# Power_Supply.net
KiCad netlist of a schematic drawn in Altium Designer
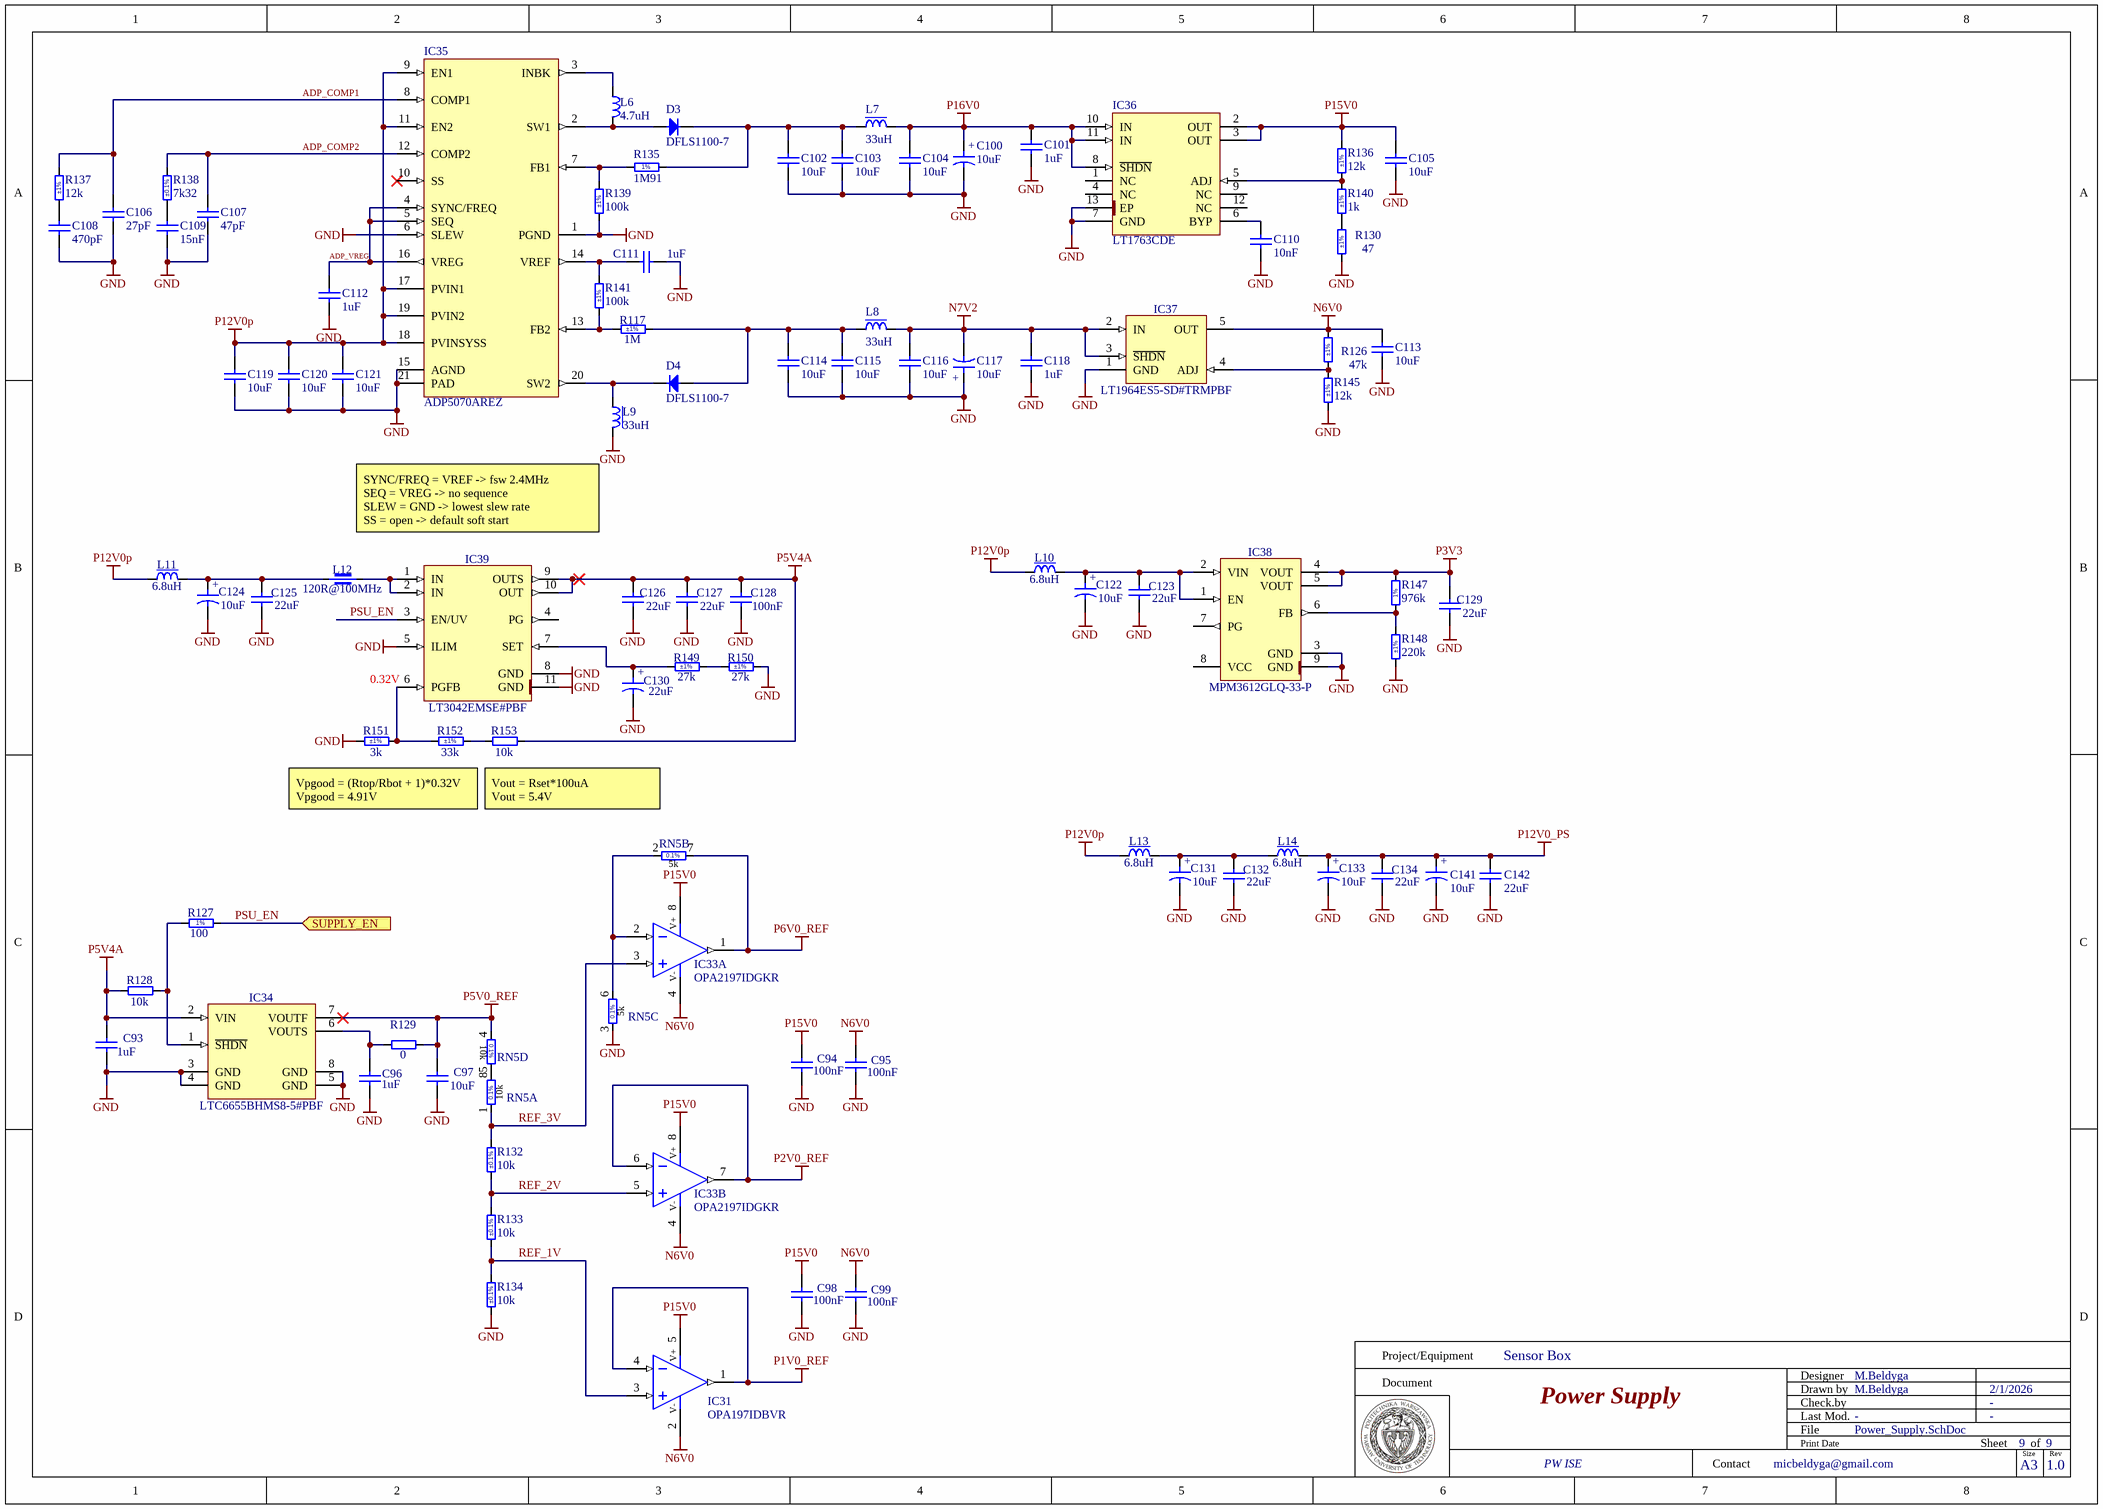
[diagram p0: Power_Supply.SchDoc]

(export (version "E")
  (design (tool "Eeschema 10.0.6"))
  (components
    (comp (ref "C93")
      (value "1uF")
      (footprint "CAPC1608X87N")
      (description "Non-polarised capacitor")
      (fields
        (field (name "PART NUMBER") "CC0603_1UF_25V_10%_X7R")
        (field (name "VOLTAGE") "25V")
        (field (name "AUTHOR") "CERN DEM JLC")
      )
      (libsource (lib "Capacitors") (part "Capacitor - non polarized"))
    )
    (comp (ref "C94")
      (value "100nF")
      (footprint "CAPC1005X55N")
      (description "Non-polarised capacitor")
      (fields
        (field (name "PART NUMBER") "CC0402_100NF_16V_10%_X5R")
        (field (name "VOLTAGE") "16V")
        (field (name "AUTHOR") "CERN DEM JLC")
      )
      (libsource (lib "Capacitors") (part "Capacitor - non polarized"))
    )
    (comp (ref "C95")
      (value "100nF")
      (footprint "CAPC1005X55N")
      (description "Non-polarised capacitor")
      (fields
        (field (name "PART NUMBER") "CC0402_100NF_16V_10%_X5R")
        (field (name "VOLTAGE") "16V")
        (field (name "AUTHOR") "CERN DEM JLC")
      )
      (libsource (lib "Capacitors") (part "Capacitor - non polarized"))
    )
    (comp (ref "C96")
      (value "1uF")
      (footprint "CAPC1608X87N")
      (description "Non-polarised capacitor")
      (fields
        (field (name "PART NUMBER") "CC0603_1UF_25V_10%_X7R")
        (field (name "VOLTAGE") "25V")
        (field (name "AUTHOR") "CERN DEM JLC")
      )
      (libsource (lib "Capacitors") (part "Capacitor - non polarized"))
    )
    (comp (ref "C97")
      (value "10uF")
      (footprint "CAPC1608X80N")
      (description "Non-polarised capacitor")
      (fields
        (field (name "PART NUMBER") "CC0603_10UF_16V_20%_X5R")
        (field (name "VOLTAGE") "16V")
        (field (name "AUTHOR") "CERN DEM MR")
      )
      (libsource (lib "Capacitors") (part "Capacitor - non polarized"))
    )
    (comp (ref "C98")
      (value "100nF")
      (footprint "CAPC1005X55N")
      (description "Non-polarised capacitor")
      (fields
        (field (name "PART NUMBER") "CC0402_100NF_16V_10%_X5R")
        (field (name "VOLTAGE") "16V")
        (field (name "AUTHOR") "CERN DEM JLC")
      )
      (libsource (lib "Capacitors") (part "Capacitor - non polarized"))
    )
    (comp (ref "C99")
      (value "100nF")
      (footprint "CAPC1005X55N")
      (description "Non-polarised capacitor")
      (fields
        (field (name "PART NUMBER") "CC0402_100NF_16V_10%_X5R")
        (field (name "VOLTAGE") "16V")
        (field (name "AUTHOR") "CERN DEM JLC")
      )
      (libsource (lib "Capacitors") (part "Capacitor - non polarized"))
    )
    (comp (ref "C100")
      (value "10uF")
      (footprint "CAPMP3216X180N")
      (description "Polarised capacitor")
      (fields
        (field (name "PART NUMBER") "CTE3216-18_10UF_16V_20%_AVX_TCJ")
        (field (name "VOLTAGE") "16V")
        (field (name "AUTHOR") "CERN DEM JLC")
      )
      (libsource (lib "Capacitors") (part "Capacitor - polarized"))
    )
    (comp (ref "C101")
      (value "1uF")
      (footprint "CAPC1608X87N")
      (description "Non-polarised capacitor")
      (fields
        (field (name "PART NUMBER") "CC0603_1UF_25V_10%_X7R")
        (field (name "VOLTAGE") "25V")
        (field (name "AUTHOR") "CERN DEM JLC")
      )
      (libsource (lib "Capacitors") (part "Capacitor - non polarized"))
    )
    (comp (ref "C102")
      (value "10uF")
      (footprint "CAPC1709X100N")
      (description "Non-polarised capacitor")
      (fields
        (field (name "PART NUMBER") "CC0603_10UF_25V_20%_X5R")
        (field (name "VOLTAGE") "25V")
        (field (name "AUTHOR") "CERN DEM BC")
      )
      (libsource (lib "Capacitors") (part "Capacitor - non polarized"))
    )
    (comp (ref "C103")
      (value "10uF")
      (footprint "CAPC1709X100N")
      (description "Non-polarised capacitor")
      (fields
        (field (name "PART NUMBER") "CC0603_10UF_25V_20%_X5R")
        (field (name "VOLTAGE") "25V")
        (field (name "AUTHOR") "CERN DEM BC")
      )
      (libsource (lib "Capacitors") (part "Capacitor - non polarized"))
    )
    (comp (ref "C104")
      (value "10uF")
      (footprint "CAPC1709X100N")
      (description "Non-polarised capacitor")
      (fields
        (field (name "PART NUMBER") "CC0603_10UF_25V_20%_X5R")
        (field (name "VOLTAGE") "25V")
        (field (name "AUTHOR") "CERN DEM BC")
      )
      (libsource (lib "Capacitors") (part "Capacitor - non polarized"))
    )
    (comp (ref "C105")
      (value "10uF")
      (footprint "CAPC1709X100N")
      (description "Non-polarised capacitor")
      (fields
        (field (name "PART NUMBER") "CC0603_10UF_25V_20%_X5R")
        (field (name "VOLTAGE") "25V")
        (field (name "AUTHOR") "CERN DEM BC")
      )
      (libsource (lib "Capacitors") (part "Capacitor - non polarized"))
    )
    (comp (ref "C106")
      (value "27pF")
      (footprint "CAPC1005X55N")
      (description "Non-polarised capacitor")
      (fields
        (field (name "PART NUMBER") "CC0402_27PF_50V_5%_C0G")
        (field (name "VOLTAGE") "50V")
        (field (name "AUTHOR") "CERN DEM JLC")
      )
      (libsource (lib "Capacitors") (part "Capacitor - non polarized"))
    )
    (comp (ref "C107")
      (value "47pF")
      (footprint "CAPC1005X55N")
      (description "Non-polarised capacitor")
      (fields
        (field (name "PART NUMBER") "CC0402_47PF_50V_5%_C0G")
        (field (name "VOLTAGE") "50V")
        (field (name "AUTHOR") "CERN DEM JLC")
      )
      (libsource (lib "Capacitors") (part "Capacitor - non polarized"))
    )
    (comp (ref "C108")
      (value "470pF")
      (footprint "CAPC1005X55N")
      (description "Non-polarised capacitor")
      (fields
        (field (name "PART NUMBER") "CC0402_470PF_50V_10%_X7R")
        (field (name "VOLTAGE") "50V")
        (field (name "AUTHOR") "CERN DEM JLC")
      )
      (libsource (lib "Capacitors") (part "Capacitor - non polarized"))
    )
    (comp (ref "C109")
      (value "15nF")
      (footprint "CAPC1005X55N")
      (description "Non-polarised capacitor")
      (fields
        (field (name "PART NUMBER") "CC0402_15NF_50V_5%_X7R")
        (field (name "VOLTAGE") "50V")
        (field (name "AUTHOR") "CERN DEM BC")
      )
      (libsource (lib "Capacitors") (part "Capacitor - non polarized"))
    )
    (comp (ref "C110")
      (value "10nF")
      (footprint "CAPC1005X55N")
      (description "Non-polarised capacitor")
      (fields
        (field (name "PART NUMBER") "CC0402_10NF_50V_5%_X7R")
        (field (name "VOLTAGE") "50V")
        (field (name "AUTHOR") "CERN DEM BC")
      )
      (libsource (lib "Capacitors") (part "Capacitor - non polarized"))
    )
    (comp (ref "C111")
      (value "1uF")
      (footprint "CAPC1608X87N")
      (description "Non-polarised capacitor")
      (fields
        (field (name "PART NUMBER") "CC0603_1UF_25V_10%_X7R")
        (field (name "VOLTAGE") "25V")
        (field (name "AUTHOR") "CERN DEM JLC")
      )
      (libsource (lib "Capacitors") (part "Capacitor - non polarized"))
    )
    (comp (ref "C112")
      (value "1uF")
      (footprint "CAPC1608X87N")
      (description "Non-polarised capacitor")
      (fields
        (field (name "PART NUMBER") "CC0603_1UF_25V_10%_X7R")
        (field (name "VOLTAGE") "25V")
        (field (name "AUTHOR") "CERN DEM JLC")
      )
      (libsource (lib "Capacitors") (part "Capacitor - non polarized"))
    )
    (comp (ref "C113")
      (value "10uF")
      (footprint "CAPC1709X100N")
      (description "Non-polarised capacitor")
      (fields
        (field (name "PART NUMBER") "CC0603_10UF_25V_20%_X5R")
        (field (name "VOLTAGE") "25V")
        (field (name "AUTHOR") "CERN DEM BC")
      )
      (libsource (lib "Capacitors") (part "Capacitor - non polarized"))
    )
    (comp (ref "C114")
      (value "10uF")
      (footprint "CAPC1709X100N")
      (description "Non-polarised capacitor")
      (fields
        (field (name "PART NUMBER") "CC0603_10UF_25V_20%_X5R")
        (field (name "VOLTAGE") "25V")
        (field (name "AUTHOR") "CERN DEM BC")
      )
      (libsource (lib "Capacitors") (part "Capacitor - non polarized"))
    )
    (comp (ref "C115")
      (value "10uF")
      (footprint "CAPC1709X100N")
      (description "Non-polarised capacitor")
      (fields
        (field (name "PART NUMBER") "CC0603_10UF_25V_20%_X5R")
        (field (name "VOLTAGE") "25V")
        (field (name "AUTHOR") "CERN DEM BC")
      )
      (libsource (lib "Capacitors") (part "Capacitor - non polarized"))
    )
    (comp (ref "C116")
      (value "10uF")
      (footprint "CAPC1709X100N")
      (description "Non-polarised capacitor")
      (fields
        (field (name "PART NUMBER") "CC0603_10UF_25V_20%_X5R")
        (field (name "VOLTAGE") "25V")
        (field (name "AUTHOR") "CERN DEM BC")
      )
      (libsource (lib "Capacitors") (part "Capacitor - non polarized"))
    )
    (comp (ref "C117")
      (value "10uF")
      (footprint "CAPMP3216X180N")
      (description "Polarised capacitor")
      (fields
        (field (name "PART NUMBER") "CTE3216-18_10UF_16V_20%_AVX_TCJ")
        (field (name "VOLTAGE") "16V")
        (field (name "AUTHOR") "CERN DEM JLC")
      )
      (libsource (lib "Capacitors") (part "Capacitor - polarized"))
    )
    (comp (ref "C118")
      (value "1uF")
      (footprint "CAPC1608X87N")
      (description "Non-polarised capacitor")
      (fields
        (field (name "PART NUMBER") "CC0603_1UF_25V_10%_X7R")
        (field (name "VOLTAGE") "25V")
        (field (name "AUTHOR") "CERN DEM JLC")
      )
      (libsource (lib "Capacitors") (part "Capacitor - non polarized"))
    )
    (comp (ref "C119")
      (value "10uF")
      (footprint "CAPC1709X100N")
      (description "Non-polarised capacitor")
      (fields
        (field (name "PART NUMBER") "CC0603_10UF_25V_20%_X5R")
        (field (name "VOLTAGE") "25V")
        (field (name "AUTHOR") "CERN DEM BC")
      )
      (libsource (lib "Capacitors") (part "Capacitor - non polarized"))
    )
    (comp (ref "C120")
      (value "10uF")
      (footprint "CAPC1709X100N")
      (description "Non-polarised capacitor")
      (fields
        (field (name "PART NUMBER") "CC0603_10UF_25V_20%_X5R")
        (field (name "VOLTAGE") "25V")
        (field (name "AUTHOR") "CERN DEM BC")
      )
      (libsource (lib "Capacitors") (part "Capacitor - non polarized"))
    )
    (comp (ref "C121")
      (value "10uF")
      (footprint "CAPC1709X100N")
      (description "Non-polarised capacitor")
      (fields
        (field (name "PART NUMBER") "CC0603_10UF_25V_20%_X5R")
        (field (name "VOLTAGE") "25V")
        (field (name "AUTHOR") "CERN DEM BC")
      )
      (libsource (lib "Capacitors") (part "Capacitor - non polarized"))
    )
    (comp (ref "C122")
      (value "10uF")
      (footprint "CAPMP3216X180N")
      (description "Polarised capacitor")
      (fields
        (field (name "PART NUMBER") "CTE3216-18_10UF_16V_20%_AVX_TCJ")
        (field (name "VOLTAGE") "16V")
        (field (name "AUTHOR") "CERN DEM JLC")
      )
      (libsource (lib "Capacitors") (part "Capacitor - polarized"))
    )
    (comp (ref "C123")
      (value "22uF")
      (footprint "CAPC2012X135N")
      (description "Non-polarised capacitor")
      (fields
        (field (name "PART NUMBER") "CC0805_22UF_16V_10%_X5R")
        (field (name "VOLTAGE") "16V")
        (field (name "AUTHOR") "CERN DEM JLC")
      )
      (libsource (lib "Capacitors") (part "Capacitor - non polarized"))
    )
    (comp (ref "C124")
      (value "10uF")
      (footprint "CAPMP3216X180N")
      (description "Polarised capacitor")
      (fields
        (field (name "PART NUMBER") "CTE3216-18_10UF_16V_20%_AVX_TCJ")
        (field (name "VOLTAGE") "16V")
        (field (name "AUTHOR") "CERN DEM JLC")
      )
      (libsource (lib "Capacitors") (part "Capacitor - polarized"))
    )
    (comp (ref "C125")
      (value "22uF")
      (footprint "CAPC2012X135N")
      (description "Non-polarised capacitor")
      (fields
        (field (name "PART NUMBER") "CC0805_22UF_16V_10%_X5R")
        (field (name "VOLTAGE") "16V")
        (field (name "AUTHOR") "CERN DEM JLC")
      )
      (libsource (lib "Capacitors") (part "Capacitor - non polarized"))
    )
    (comp (ref "C126")
      (value "22uF")
      (footprint "CAPC2012X135N")
      (description "Non-polarised capacitor")
      (fields
        (field (name "PART NUMBER") "CC0805_22UF_16V_10%_X5R")
        (field (name "VOLTAGE") "16V")
        (field (name "AUTHOR") "CERN DEM JLC")
      )
      (libsource (lib "Capacitors") (part "Capacitor - non polarized"))
    )
    (comp (ref "C127")
      (value "22uF")
      (footprint "CAPC2012X135N")
      (description "Non-polarised capacitor")
      (fields
        (field (name "PART NUMBER") "CC0805_22UF_16V_10%_X5R")
        (field (name "VOLTAGE") "16V")
        (field (name "AUTHOR") "CERN DEM JLC")
      )
      (libsource (lib "Capacitors") (part "Capacitor - non polarized"))
    )
    (comp (ref "C128")
      (value "100nF")
      (footprint "CAPC1005X55N")
      (description "Non-polarised capacitor")
      (fields
        (field (name "PART NUMBER") "CC0402_100NF_16V_10%_X5R")
        (field (name "VOLTAGE") "16V")
        (field (name "AUTHOR") "CERN DEM JLC")
      )
      (libsource (lib "Capacitors") (part "Capacitor - non polarized"))
    )
    (comp (ref "C129")
      (value "22uF")
      (footprint "CAPC2012X135N")
      (description "Non-polarised capacitor")
      (fields
        (field (name "PART NUMBER") "CC0805_22UF_16V_10%_X5R")
        (field (name "VOLTAGE") "16V")
        (field (name "AUTHOR") "CERN DEM JLC")
      )
      (libsource (lib "Capacitors") (part "Capacitor - non polarized"))
    )
    (comp (ref "C130")
      (value "22uF")
      (footprint "CAPMP3528X210N")
      (description "Polarised capacitor")
      (fields
        (field (name "PART NUMBER") "CTE3528-21_22UF_10V_10%_LESR0700")
        (field (name "VOLTAGE") "10V")
        (field (name "AUTHOR") "CERN DEM JLC")
      )
      (libsource (lib "Capacitors") (part "Capacitor - polarized"))
    )
    (comp (ref "C131")
      (value "10uF")
      (footprint "CAPMP3216X180N")
      (description "Polarised capacitor")
      (fields
        (field (name "PART NUMBER") "CTE3216-18_10UF_16V_20%_AVX_TCJ")
        (field (name "VOLTAGE") "16V")
        (field (name "AUTHOR") "CERN DEM JLC")
      )
      (libsource (lib "Capacitors") (part "Capacitor - polarized"))
    )
    (comp (ref "C132")
      (value "22uF")
      (footprint "CAPC2012X135N")
      (description "Non-polarised capacitor")
      (fields
        (field (name "PART NUMBER") "CC0805_22UF_16V_10%_X5R")
        (field (name "VOLTAGE") "16V")
        (field (name "AUTHOR") "CERN DEM JLC")
      )
      (libsource (lib "Capacitors") (part "Capacitor - non polarized"))
    )
    (comp (ref "C133")
      (value "10uF")
      (footprint "CAPMP3216X180N")
      (description "Polarised capacitor")
      (fields
        (field (name "PART NUMBER") "CTE3216-18_10UF_16V_20%_AVX_TCJ")
        (field (name "VOLTAGE") "16V")
        (field (name "AUTHOR") "CERN DEM JLC")
      )
      (libsource (lib "Capacitors") (part "Capacitor - polarized"))
    )
    (comp (ref "C134")
      (value "22uF")
      (footprint "CAPC2012X135N")
      (description "Non-polarised capacitor")
      (fields
        (field (name "PART NUMBER") "CC0805_22UF_16V_10%_X5R")
        (field (name "VOLTAGE") "16V")
        (field (name "AUTHOR") "CERN DEM JLC")
      )
      (libsource (lib "Capacitors") (part "Capacitor - non polarized"))
    )
    (comp (ref "C141")
      (value "10uF")
      (footprint "CAPMP3216X180N")
      (description "Polarised capacitor")
      (fields
        (field (name "PART NUMBER") "CTE3216-18_10UF_16V_20%_AVX_TCJ")
        (field (name "VOLTAGE") "16V")
        (field (name "AUTHOR") "CERN DEM JLC")
      )
      (libsource (lib "Capacitors") (part "Capacitor - polarized"))
    )
    (comp (ref "C142")
      (value "22uF")
      (footprint "CAPC2012X135N")
      (description "Non-polarised capacitor")
      (fields
        (field (name "PART NUMBER") "CC0805_22UF_16V_10%_X5R")
        (field (name "VOLTAGE") "16V")
        (field (name "AUTHOR") "CERN DEM JLC")
      )
      (libsource (lib "Capacitors") (part "Capacitor - non polarized"))
    )
    (comp (ref "D3")
      (value "DFLS1100-7")
      (footprint "DIODES-INC_POWERDI123")
      (description "Diode")
      (fields
        (field (name "VOLTAGE") "100V")
        (field (name "POWER") "1A")
        (field (name "AUTHOR") "CERN DEM HF")
      )
      (libsource (lib "ICs And Semiconductors") (part "Diode"))
    )
    (comp (ref "D4")
      (value "DFLS1100-7")
      (footprint "DIODES-INC_POWERDI123")
      (description "Diode")
      (fields
        (field (name "VOLTAGE") "100V")
        (field (name "POWER") "1A")
        (field (name "AUTHOR") "CERN DEM HF")
      )
      (libsource (lib "ICs And Semiconductors") (part "Diode"))
    )
    (comp (ref "IC31")
      (value "OPA197IDBVR")
      (footprint "SOT95P280X145-5N")
      (description "Op Amp Single Precision Amplifier R-R I/O ±18V/36V 5-Pin SOT-23 T/R")
      (fields (field (name "MANUFACTURER") "Texas Instruments"))
      (libsource (lib "mb") (part "OPA197IDBVR"))
    )
    (comp (ref "IC33")
      (value "OPA2197IDGKR")
      (footprint "SOP65P490X110-8N")
      (description "36-V, Precision, Rail-to-Rail Input Output, Low Offset Voltage Op Amp 8-VSSOP")
      (fields (field (name "AUTHOR") "GK"))
      (libsource (lib "ICs_Analog_Interfaces") (part "OA_OPA2197IDGKR"))
    )
    (comp (ref "IC34")
      (value "LTC6655BHMS8-5#PBF")
      (footprint "SOP65P490X110-8N")
      (description "0.25ppm Noise, Low Drift Precision Buffered Voltage Reference")
      (fields (field (name "AUTHOR") "CERN DEM JLC"))
      (libsource (lib "ICs And Semiconductors") (part "LTC6655"))
    )
    (comp (ref "IC35")
      (value "ADP5070AREZ")
      (footprint "SOP65P640X120-21N-R305X425")
      (description "1A/0.6A, DC-to-DC Switching Regulator with Independent Positive and Negative Outputs")
      (fields
        (field (name "MANUFACTURER") "ANALOG DEVICES")
        (field (name "MANUFACTURER PART NUMBER") "ADP5070ARE")
        (field (name "AUTHOR") "CERN DEM JLC")
      )
      (libsource (lib "mb") (part "ADP5070AREZ"))
    )
    (comp (ref "IC36")
      (value "LT1763CDE")
      (footprint "SON50P300X400X80-13N-R180X340")
      (description "1.22V to 20V 500mA, Low Noise, LDO Adjustable Micropower Regulator")
      (fields (field (name "MANUFACTURER") "LINEAR TECHNOLOGY") (field (name "AUTHOR") "CERN DEM HF"))
      (libsource (lib "ICs And Semiconductors") (part "LT1763xDE_a"))
    )
    (comp (ref "IC37")
      (value "LT1964ES5-SD#TRMPBF")
      (footprint "SOT95P280X100-5N")
      (description "200mA, Low Noise, Low Dropout Negative Micropower Regulator")
      (fields (field (name "MANUFACTURER") "LINEAR TECHNOLOGY") (field (name "AUTHOR") "CERN DEM JLC"))
      (libsource (lib "ICs And Semiconductors") (part "LT1964-SD"))
    )
    (comp (ref "IC38")
      (value "MPM3612GLQ-33-P")
      (footprint "MPS_MPM3612")
      (description "3V to 22V Input, 1A, Ultra-Low 5µA IQ Power Module")
      (fields
        (field (name "MANUFACTURER") "MPS (MONOLITIC  POWER SYSTEMS)")
        (field (name "AUTHOR") "CERN DEM HF")
      )
      (libsource (lib "ICs And Semiconductors") (part "MPM3612"))
    )
    (comp (ref "IC39")
      (value "LT3042EMSE#PBF")
      (footprint "SOP50P490X110-11N-R168X198")
      (description "20V, 200mA, Ultralow Noise, Ultrahigh PSRR RF Linear Regulator")
      (fields (field (name "AUTHOR") "CERN DEM MR"))
      (libsource (lib "ICs And Semiconductors") (part "LT3042"))
    )
    (comp (ref "L6")
      (value "4.7uH")
      (footprint "IND_COILCRAFT_EPL3015")
      (description "Inductor")
      (fields
        (field (name "PART NUMBER") "IND_4.7UH_20%_COILCRAFT_EPL3015")
        (field (name "POWER") "1A")
        (field (name "AUTHOR") "CERN DEM BC")
      )
      (libsource (lib "Inductors & Transformers") (part "Inductor"))
    )
    (comp (ref "L7")
      (value "33uH")
      (footprint "IND_WURTH_WE-TPC_4828")
      (description "Inductor With Core")
      (fields
        (field (name "PART NUMBER") "IND_33UH_30%_WURTH_WE-TPC_744043330")
        (field (name "POWER") "820mA")
        (field (name "AUTHOR") "CERN DEM JLC")
      )
      (libsource (lib "Inductors & Transformers") (part "Inductor With Magnetic core"))
    )
    (comp (ref "L8")
      (value "33uH")
      (footprint "IND_WURTH_WE-TPC_4828")
      (description "Inductor With Core")
      (fields
        (field (name "PART NUMBER") "IND_33UH_30%_WURTH_WE-TPC_744043330")
        (field (name "POWER") "820mA")
        (field (name "AUTHOR") "CERN DEM JLC")
      )
      (libsource (lib "Inductors & Transformers") (part "Inductor With Magnetic core"))
    )
    (comp (ref "L9")
      (value "33uH")
      (footprint "IND_WURTH_WE-TPC_4828")
      (description "Inductor With Core")
      (fields
        (field (name "PART NUMBER") "IND_33UH_30%_WURTH_WE-TPC_744043330")
        (field (name "POWER") "820mA")
        (field (name "AUTHOR") "CERN DEM JLC")
      )
      (libsource (lib "") (part "Inductor With Magnetic core_1"))
    )
    (comp (ref "L10")
      (value "6.8uH")
      (footprint "IND_COILCRAFT_XAL4030")
      (description "Inductor With Core")
      (fields
        (field (name "PART NUMBER") "IND_6.8UH_20%_COILCRAFT_XAL4030")
        (field (name "POWER") "3A")
        (field (name "AUTHOR") "CERN DEM MR")
      )
      (libsource (lib "Inductors & Transformers") (part "Inductor With Magnetic core"))
    )
    (comp (ref "L11")
      (value "6.8uH")
      (footprint "IND_COILCRAFT_XAL4030")
      (description "Inductor With Core")
      (fields
        (field (name "PART NUMBER") "IND_6.8UH_20%_COILCRAFT_XAL4030")
        (field (name "POWER") "3A")
        (field (name "AUTHOR") "CERN DEM MR")
      )
      (libsource (lib "Inductors & Transformers") (part "Inductor With Magnetic core"))
    )
    (comp (ref "L12")
      (value "120R@100MHz")
      (footprint "INDC1608X65N")
      (fields
        (field (name "PART NUMBER") "IND0603_MURATA_BLM18SG121TN1D")
        (field (name "POWER") "3A")
        (field (name "TOLERANCE") "±25%")
        (field (name "AUTHOR") "CERN DEM JLC")
      )
      (libsource (lib "Inductors & Transformers") (part "Ferrite Bead"))
    )
    (comp (ref "L13")
      (value "6.8uH")
      (footprint "IND_COILCRAFT_XAL4030")
      (description "Inductor With Core")
      (fields
        (field (name "PART NUMBER") "IND_6.8UH_20%_COILCRAFT_XAL4030")
        (field (name "POWER") "3A")
        (field (name "AUTHOR") "CERN DEM MR")
      )
      (libsource (lib "Inductors & Transformers") (part "Inductor With Magnetic core"))
    )
    (comp (ref "L14")
      (value "6.8uH")
      (footprint "IND_COILCRAFT_XAL4030")
      (description "Inductor With Core")
      (fields
        (field (name "PART NUMBER") "IND_6.8UH_20%_COILCRAFT_XAL4030")
        (field (name "POWER") "3A")
        (field (name "AUTHOR") "CERN DEM MR")
      )
      (libsource (lib "Inductors & Transformers") (part "Inductor With Magnetic core"))
    )
    (comp (ref "R117")
      (value "1M")
      (footprint "RESC1005X40N")
      (description "Resistor - 1%")
      (fields
        (field (name "TOLERANCE") "±1%")
        (field (name "PART NUMBER") "R0402_1M_1%_0.0625W_100PPM")
        (field (name "POWER") "0.0625W")
        (field (name "AUTHOR") "CERN DEM JLC")
      )
      (libsource (lib "") (part "Resistor - 1%_1"))
    )
    (comp (ref "R126")
      (value "47k")
      (footprint "RESC1005X40N")
      (description "Resistor - 1%")
      (fields
        (field (name "TOLERANCE") "±1%")
        (field (name "PART NUMBER") "R0402_47K_1%_0.0625W_100PPM")
        (field (name "POWER") "0.0625W")
        (field (name "AUTHOR") "CERN DEM JLC")
      )
      (libsource (lib "") (part "Resistor - 1%_1"))
    )
    (comp (ref "R127")
      (value "100")
      (footprint "RESC1005X40N")
      (description "Resistor - 1%")
      (fields
        (field (name "PART NUMBER") "R0402_100R_1%_0.0625W_100PPM")
        (field (name "POWER") "0.0625W")
        (field (name "AUTHOR") "CERN DEM JLC")
      )
      (libsource (lib "Resistors") (part "Resistor - 1%"))
    )
    (comp (ref "R128")
      (value "10k")
      (footprint "RESC1005X35N")
      (description "Resistor - 0.1%")
      (fields
        (field (name "PART NUMBER") "R0402_10K_0.1%_0.063W_25PPM")
        (field (name "POWER") "0.063W")
        (field (name "AUTHOR") "CERN DEM JMW")
      )
      (libsource (lib "Resistors") (part "Resistor - 0.1%"))
    )
    (comp (ref "R129")
      (value "0")
      (footprint "RESC1005X40N")
      (description "Resistor")
      (fields
        (field (name "PART NUMBER") "R0402_0R_JUMPER")
        (field (name "MANUFACTURER") "GENERIC")
        (field (name "AUTHOR") "CERN DEM JLC")
      )
      (libsource (lib "Resistors") (part "Resistor"))
    )
    (comp (ref "R130")
      (value "47")
      (footprint "RESC1608X55N")
      (description "Resistor - 1%")
      (fields
        (field (name "TOLERANCE") "±1%")
        (field (name "PART NUMBER") "R0603_47R_1%_0.1W_100PPM")
        (field (name "POWER") "0.1W")
        (field (name "AUTHOR") "CERN DEM JLC")
      )
      (libsource (lib "") (part "Resistor - 1%_1"))
    )
    (comp (ref "R132")
      (value "10k")
      (footprint "RESC1005X35N")
      (description "Resistor - 0.1%")
      (fields
        (field (name "TOLERANCE") "±0.1%")
        (field (name "PART NUMBER") "R0402_10K_0.1%_0.063W_25PPM")
        (field (name "POWER") "0.063W")
        (field (name "AUTHOR") "CERN DEM JMW")
      )
      (libsource (lib "Resistors") (part "Resistor - 0.1%"))
    )
    (comp (ref "R133")
      (value "10k")
      (footprint "RESC1005X35N")
      (description "Resistor - 0.1%")
      (fields
        (field (name "TOLERANCE") "±0.1%")
        (field (name "PART NUMBER") "R0402_10K_0.1%_0.063W_25PPM")
        (field (name "POWER") "0.063W")
        (field (name "AUTHOR") "CERN DEM JMW")
      )
      (libsource (lib "Resistors") (part "Resistor - 0.1%"))
    )
    (comp (ref "R134")
      (value "10k")
      (footprint "RESC1005X35N")
      (description "Resistor - 0.1%")
      (fields
        (field (name "TOLERANCE") "±0.1%")
        (field (name "PART NUMBER") "R0402_10K_0.1%_0.063W_25PPM")
        (field (name "POWER") "0.063W")
        (field (name "AUTHOR") "CERN DEM JMW")
      )
      (libsource (lib "Resistors") (part "Resistor - 0.1%"))
    )
    (comp (ref "R135")
      (value "1M91")
      (footprint "RESC1005X40N")
      (description "RES 1M91 OHM 1% 1/16W 0402")
      (fields
        (field (name "PART NUMBER") "R0402_1M91_1%_0.0625W")
        (field (name "POWER") "0.0625W")
        (field (name "AUTHOR") "Michal Beldyga")
      )
      (libsource (lib "Resistors") (part "Resistor - 1%"))
    )
    (comp (ref "R136")
      (value "12k")
      (footprint "RESC1005X40N")
      (description "Resistor - 1%")
      (fields
        (field (name "TOLERANCE") "±1%")
        (field (name "PART NUMBER") "R0402_12K_1%_0.0625W_100PPM")
        (field (name "POWER") "0.0625W")
        (field (name "AUTHOR") "CERN DEM JLC")
      )
      (libsource (lib "") (part "Resistor - 1%_1"))
    )
    (comp (ref "R137")
      (value "12k")
      (footprint "RESC1005X40N")
      (description "Resistor - 1%")
      (fields
        (field (name "TOLERANCE") "±1%")
        (field (name "PART NUMBER") "R0402_12K_1%_0.0625W_100PPM")
        (field (name "POWER") "0.0625W")
        (field (name "AUTHOR") "CERN DEM JLC")
      )
      (libsource (lib "") (part "Resistor - 1%_1"))
    )
    (comp (ref "R138")
      (value "7k32")
      (footprint "RESC1608X55N")
      (description "Resistor - 0.1%")
      (fields
        (field (name "TOLERANCE") "±0.1%")
        (field (name "PART NUMBER") "R0603_7K32_0.1%_0.063W_10PPM")
        (field (name "POWER") "0.063W")
        (field (name "AUTHOR") "CERN DEM JLC")
      )
      (libsource (lib "Resistors") (part "Resistor - 0.1%"))
    )
    (comp (ref "R139")
      (value "100k")
      (footprint "RESC1005X40N")
      (description "Resistor - 1%")
      (fields
        (field (name "TOLERANCE") "±1%")
        (field (name "PART NUMBER") "R0402_100K_1%_0.0625W_100PPM")
        (field (name "POWER") "0.0625W")
        (field (name "AUTHOR") "CERN DEM JLC")
      )
      (libsource (lib "") (part "Resistor - 1%_1"))
    )
    (comp (ref "R140")
      (value "1k")
      (footprint "RESC1005X40N")
      (description "Resistor - 1%")
      (fields
        (field (name "TOLERANCE") "±1%")
        (field (name "PART NUMBER") "R0402_1K_1%_0.0625W_100PPM")
        (field (name "POWER") "0.0625W")
        (field (name "AUTHOR") "CERN DEM JLC")
      )
      (libsource (lib "") (part "Resistor - 1%_1"))
    )
    (comp (ref "R141")
      (value "100k")
      (footprint "RESC1005X40N")
      (description "Resistor - 1%")
      (fields
        (field (name "TOLERANCE") "±1%")
        (field (name "PART NUMBER") "R0402_100K_1%_0.0625W_100PPM")
        (field (name "POWER") "0.0625W")
        (field (name "AUTHOR") "CERN DEM JLC")
      )
      (libsource (lib "") (part "Resistor - 1%_1"))
    )
    (comp (ref "R145")
      (value "12k")
      (footprint "RESC1005X40N")
      (description "Resistor - 1%")
      (fields
        (field (name "TOLERANCE") "±1%")
        (field (name "PART NUMBER") "R0402_12K_1%_0.0625W_100PPM")
        (field (name "POWER") "0.0625W")
        (field (name "AUTHOR") "CERN DEM JLC")
      )
      (libsource (lib "") (part "Resistor - 1%_1"))
    )
    (comp (ref "R147")
      (value "976k")
      (footprint "RESC1005X40N")
      (description "RES 976k OHM 1% 1/16W 0402")
      (fields
        (field (name "PART NUMBER") "R0402_976K_1%_0.0625W")
        (field (name "POWER") "0.0625W")
        (field (name "AUTHOR") "Michal Beldyga")
      )
      (libsource (lib "Resistors") (part "Resistor - 1%"))
    )
    (comp (ref "R148")
      (value "220k")
      (footprint "RESC1005X40N")
      (description "Resistor - 1%")
      (fields
        (field (name "TOLERANCE") "±1%")
        (field (name "PART NUMBER") "R0402_220K_1%_0.0625W_100PPM")
        (field (name "POWER") "0.0625W")
        (field (name "AUTHOR") "CERN DEM JLC")
      )
      (libsource (lib "") (part "Resistor - 1%_1"))
    )
    (comp (ref "R149")
      (value "27k")
      (footprint "RESC1005X40N")
      (description "Resistor - 1%")
      (fields
        (field (name "TOLERANCE") "±1%")
        (field (name "PART NUMBER") "R0402_27K_1%_0.0625W_100PPM")
        (field (name "POWER") "0.0625W")
        (field (name "AUTHOR") "CERN DEM JLC")
      )
      (libsource (lib "") (part "Resistor - 1%_1"))
    )
    (comp (ref "R150")
      (value "27k")
      (footprint "RESC1005X40N")
      (description "Resistor - 1%")
      (fields
        (field (name "TOLERANCE") "±1%")
        (field (name "PART NUMBER") "R0402_27K_1%_0.0625W_100PPM")
        (field (name "POWER") "0.0625W")
        (field (name "AUTHOR") "CERN DEM JLC")
      )
      (libsource (lib "") (part "Resistor - 1%_1"))
    )
    (comp (ref "R151")
      (value "3k")
      (footprint "RESC1005X40N")
      (description "Resistor - 1%")
      (fields
        (field (name "TOLERANCE") "±1%")
        (field (name "PART NUMBER") "R0402_3K_1%_0.0625W_100PPM")
        (field (name "POWER") "0.0625W")
        (field (name "AUTHOR") "CERN DEM JLC")
      )
      (libsource (lib "") (part "Resistor - 1%_1"))
    )
    (comp (ref "R152")
      (value "33k")
      (footprint "RESC1005X40N")
      (description "Resistor - 1%")
      (fields
        (field (name "TOLERANCE") "±1%")
        (field (name "PART NUMBER") "R0402_33K_1%_0.0625W_100PPM")
        (field (name "POWER") "0.0625W")
        (field (name "AUTHOR") "CERN DEM JLC")
      )
      (libsource (lib "") (part "Resistor - 1%_1"))
    )
    (comp (ref "R153")
      (value "10k")
      (footprint "RESC1005X35N")
      (description "Resistor - 0.1%")
      (fields
        (field (name "PART NUMBER") "R0402_10K_0.1%_0.063W_25PPM")
        (field (name "POWER") "0.063W")
        (field (name "AUTHOR") "CERN DEM JMW")
      )
      (libsource (lib "Resistors") (part "Resistor - 0.1%"))
    )
    (comp (ref "RN5")
      (value "10k 5K 5K 10K")
      (footprint "SOIC127P600X175-8N")
      (description "DIL8 Resistor Network 4 Resistors 10k-5k-5k-10k 0.1%")
      (fields
        (field (name "PART NUMBER") "RN_10K_5K_VISHAY_AORN2-1AT3")
        (field (name "POWER") "4x0.1W")
        (field (name "AUTHOR") "CERN DEM JLC")
      )
      (libsource (lib "Resistors") (part "RN DIL8_4xR_10k-5k-5k-10k_0.1%"))
    )
  )
  (nets
    (net (code "1") (name "/ADP_COMP1") (class "Default")
      (node (ref "C106") (pin "2") (pinfunction "2_2") (pintype "passive"))
      (node (ref "IC35") (pin "8") (pinfunction "COMP1_8") (pintype "input"))
      (node (ref "R137") (pin "2") (pinfunction "2_2") (pintype "passive"))
    )
    (net (code "2") (name "/ADP_COMP2") (class "Default")
      (node (ref "C107") (pin "2") (pinfunction "2_2") (pintype "passive"))
      (node (ref "IC35") (pin "12") (pinfunction "COMP2_12") (pintype "input"))
      (node (ref "R138") (pin "2") (pinfunction "2_2") (pintype "passive"))
    )
    (net (code "3") (name "/ADP_VREG") (class "Default")
      (node (ref "C112") (pin "2") (pinfunction "2_2") (pintype "passive"))
      (node (ref "IC35") (pin "16") (pinfunction "VREG_16") (pintype "output"))
      (node (ref "IC35") (pin "4") (pinfunction "SYNC/FREQ_4") (pintype "input"))
      (node (ref "IC35") (pin "5") (pinfunction "SEQ_5") (pintype "input"))
    )
    (net (code "4") (name "/PSU_EN") (class "Default")
      (node (ref "IC39") (pin "3") (pinfunction "EN/UV_3") (pintype "input"))
      (node (ref "R127") (pin "2") (pinfunction "2_2") (pintype "passive"))
    )
    (net (code "5") (name "/REF_1V") (class "Default")
      (node (ref "IC31") (pin "3") (pinfunction "IN+_3") (pintype "input"))
      (node (ref "R133") (pin "1") (pinfunction "1_1") (pintype "passive"))
      (node (ref "R134") (pin "2") (pinfunction "2_2") (pintype "passive"))
    )
    (net (code "6") (name "/REF_2V") (class "Default")
      (node (ref "IC33") (pin "5") (pinfunction "IN+_5") (pintype "input"))
      (node (ref "R132") (pin "1") (pinfunction "1_1") (pintype "passive"))
      (node (ref "R133") (pin "2") (pinfunction "2_2") (pintype "passive"))
    )
    (net (code "7") (name "/REF_3V") (class "Default")
      (node (ref "IC33") (pin "3") (pinfunction "IN+_3") (pintype "input"))
      (node (ref "R132") (pin "2") (pinfunction "2_2") (pintype "passive"))
      (node (ref "RN5") (pin "1") (pinfunction "1_1") (pintype "passive"))
    )
    (net (code "8") (name "GND") (class "Default")
      (node (ref "C100") (pin "2") (pinfunction "2_2") (pintype "passive"))
      (node (ref "C101") (pin "1") (pinfunction "1_1") (pintype "passive"))
      (node (ref "C102") (pin "1") (pinfunction "1_1") (pintype "passive"))
      (node (ref "C103") (pin "1") (pinfunction "1_1") (pintype "passive"))
      (node (ref "C104") (pin "1") (pinfunction "1_1") (pintype "passive"))
      (node (ref "C105") (pin "1") (pinfunction "1_1") (pintype "passive"))
      (node (ref "C106") (pin "1") (pinfunction "1_1") (pintype "passive"))
      (node (ref "C107") (pin "1") (pinfunction "1_1") (pintype "passive"))
      (node (ref "C108") (pin "1") (pinfunction "1_1") (pintype "passive"))
      (node (ref "C109") (pin "1") (pinfunction "1_1") (pintype "passive"))
      (node (ref "C110") (pin "1") (pinfunction "1_1") (pintype "passive"))
      (node (ref "C111") (pin "1") (pinfunction "1_1") (pintype "passive"))
      (node (ref "C112") (pin "1") (pinfunction "1_1") (pintype "passive"))
      (node (ref "C113") (pin "1") (pinfunction "1_1") (pintype "passive"))
      (node (ref "C114") (pin "1") (pinfunction "1_1") (pintype "passive"))
      (node (ref "C115") (pin "1") (pinfunction "1_1") (pintype "passive"))
      (node (ref "C116") (pin "1") (pinfunction "1_1") (pintype "passive"))
      (node (ref "C117") (pin "1") (pinfunction "1_1") (pintype "passive"))
      (node (ref "C118") (pin "1") (pinfunction "1_1") (pintype "passive"))
      (node (ref "C119") (pin "1") (pinfunction "1_1") (pintype "passive"))
      (node (ref "C120") (pin "1") (pinfunction "1_1") (pintype "passive"))
      (node (ref "C121") (pin "1") (pinfunction "1_1") (pintype "passive"))
      (node (ref "C122") (pin "2") (pinfunction "2_2") (pintype "passive"))
      (node (ref "C123") (pin "1") (pinfunction "1_1") (pintype "passive"))
      (node (ref "C124") (pin "2") (pinfunction "2_2") (pintype "passive"))
      (node (ref "C125") (pin "1") (pinfunction "1_1") (pintype "passive"))
      (node (ref "C126") (pin "1") (pinfunction "1_1") (pintype "passive"))
      (node (ref "C127") (pin "1") (pinfunction "1_1") (pintype "passive"))
      (node (ref "C128") (pin "1") (pinfunction "1_1") (pintype "passive"))
      (node (ref "C129") (pin "1") (pinfunction "1_1") (pintype "passive"))
      (node (ref "C130") (pin "2") (pinfunction "2_2") (pintype "passive"))
      (node (ref "C131") (pin "2") (pinfunction "2_2") (pintype "passive"))
      (node (ref "C132") (pin "1") (pinfunction "1_1") (pintype "passive"))
      (node (ref "C133") (pin "2") (pinfunction "2_2") (pintype "passive"))
      (node (ref "C134") (pin "1") (pinfunction "1_1") (pintype "passive"))
      (node (ref "C141") (pin "2") (pinfunction "2_2") (pintype "passive"))
      (node (ref "C142") (pin "1") (pinfunction "1_1") (pintype "passive"))
      (node (ref "C93") (pin "1") (pinfunction "1_1") (pintype "passive"))
      (node (ref "C94") (pin "1") (pinfunction "1_1") (pintype "passive"))
      (node (ref "C95") (pin "1") (pinfunction "1_1") (pintype "passive"))
      (node (ref "C96") (pin "1") (pinfunction "1_1") (pintype "passive"))
      (node (ref "C97") (pin "1") (pinfunction "1_1") (pintype "passive"))
      (node (ref "C98") (pin "1") (pinfunction "1_1") (pintype "passive"))
      (node (ref "C99") (pin "1") (pinfunction "1_1") (pintype "passive"))
      (node (ref "IC34") (pin "3") (pinfunction "GND_3") (pintype "power_in"))
      (node (ref "IC34") (pin "4") (pinfunction "GND_4") (pintype "power_in"))
      (node (ref "IC34") (pin "5") (pinfunction "GND_5") (pintype "power_in"))
      (node (ref "IC34") (pin "8") (pinfunction "GND_8") (pintype "power_in"))
      (node (ref "IC35") (pin "1") (pinfunction "PGND_1") (pintype "power_in"))
      (node (ref "IC35") (pin "15") (pinfunction "AGND_15") (pintype "power_in"))
      (node (ref "IC35") (pin "21") (pinfunction "PAD_21") (pintype "power_in"))
      (node (ref "IC35") (pin "6") (pinfunction "SLEW_6") (pintype "input"))
      (node (ref "IC36") (pin "13") (pinfunction "EP_13") (pintype "power_in"))
      (node (ref "IC36") (pin "7") (pinfunction "GND_7") (pintype "power_in"))
      (node (ref "IC37") (pin "1") (pinfunction "GND_1") (pintype "power_in"))
      (node (ref "IC38") (pin "3") (pinfunction "GND_3") (pintype "power_in"))
      (node (ref "IC38") (pin "9") (pinfunction "GND_9") (pintype "power_in"))
      (node (ref "IC39") (pin "11") (pinfunction "GND_11") (pintype "power_in"))
      (node (ref "IC39") (pin "5") (pinfunction "ILIM_5") (pintype "input"))
      (node (ref "IC39") (pin "8") (pinfunction "GND_8") (pintype "power_in"))
      (node (ref "L9") (pin "2") (pinfunction "2_2") (pintype "passive"))
      (node (ref "R130") (pin "1") (pinfunction "1_1") (pintype "passive"))
      (node (ref "R134") (pin "1") (pinfunction "1_1") (pintype "passive"))
      (node (ref "R139") (pin "1") (pinfunction "1_1") (pintype "passive"))
      (node (ref "R145") (pin "1") (pinfunction "1_1") (pintype "passive"))
      (node (ref "R148") (pin "1") (pinfunction "1_1") (pintype "passive"))
      (node (ref "R150") (pin "2") (pinfunction "2_2") (pintype "passive"))
      (node (ref "R151") (pin "1") (pinfunction "1_1") (pintype "passive"))
      (node (ref "RN5") (pin "3") (pinfunction "3_3") (pintype "passive"))
    )
    (net (code "9") (name "N6V0") (class "Default")
      (node (ref "C113") (pin "2") (pinfunction "2_2") (pintype "passive"))
      (node (ref "C95") (pin "2") (pinfunction "2_2") (pintype "passive"))
      (node (ref "C99") (pin "2") (pinfunction "2_2") (pintype "passive"))
      (node (ref "IC31") (pin "2") (pinfunction "V-_2") (pintype "power_in"))
      (node (ref "IC33") (pin "4") (pinfunction "V-_4") (pintype "power_in"))
      (node (ref "IC37") (pin "5") (pinfunction "OUT_5") (pintype "power_in"))
      (node (ref "R126") (pin "2") (pinfunction "2_2") (pintype "passive"))
    )
    (net (code "10") (name "N7V2") (class "Default")
      (node (ref "C116") (pin "2") (pinfunction "2_2") (pintype "passive"))
      (node (ref "C117") (pin "2") (pinfunction "2_2") (pintype "passive"))
      (node (ref "C118") (pin "2") (pinfunction "2_2") (pintype "passive"))
      (node (ref "IC37") (pin "2") (pinfunction "IN_2") (pintype "input"))
      (node (ref "IC37") (pin "3") (pinfunction "~{SHDN}_3") (pintype "input"))
      (node (ref "L8") (pin "2") (pinfunction "2_2") (pintype "passive"))
    )
    (net (code "11") (name "Net-(C108-Pad2)") (class "Default")
      (node (ref "C108") (pin "2") (pinfunction "2_2") (pintype "passive"))
      (node (ref "R137") (pin "1") (pinfunction "1_1") (pintype "passive"))
    )
    (net (code "12") (name "Net-(C109-Pad2)") (class "Default")
      (node (ref "C109") (pin "2") (pinfunction "2_2") (pintype "passive"))
      (node (ref "R138") (pin "1") (pinfunction "1_1") (pintype "passive"))
    )
    (net (code "13") (name "Net-(C124-Pad1)") (class "Default")
      (node (ref "C124") (pin "1") (pinfunction "1_1") (pintype "passive"))
      (node (ref "C125") (pin "2") (pinfunction "2_2") (pintype "passive"))
      (node (ref "L11") (pin "2") (pinfunction "2_2") (pintype "passive"))
      (node (ref "L12") (pin "1") (pinfunction "1_1") (pintype "passive"))
    )
    (net (code "14") (name "Net-(C131-Pad1)") (class "Default")
      (node (ref "C131") (pin "1") (pinfunction "1_1") (pintype "passive"))
      (node (ref "C132") (pin "2") (pinfunction "2_2") (pintype "passive"))
      (node (ref "L13") (pin "2") (pinfunction "2_2") (pintype "passive"))
      (node (ref "L14") (pin "1") (pinfunction "1_1") (pintype "passive"))
    )
    (net (code "15") (name "Net-(D3-A)") (class "Default")
      (node (ref "D3") (pin "2") (pinfunction "A_2") (pintype "passive"))
      (node (ref "IC35") (pin "2") (pinfunction "SW1_2") (pintype "output"))
      (node (ref "L6") (pin "2") (pinfunction "2_2") (pintype "passive"))
    )
    (net (code "16") (name "Net-(D3-C)") (class "Default")
      (node (ref "C102") (pin "2") (pinfunction "2_2") (pintype "passive"))
      (node (ref "C103") (pin "2") (pinfunction "2_2") (pintype "passive"))
      (node (ref "D3") (pin "1") (pinfunction "C_1") (pintype "passive"))
      (node (ref "L7") (pin "1") (pinfunction "1_1") (pintype "passive"))
      (node (ref "R135") (pin "2") (pinfunction "2_2") (pintype "passive"))
    )
    (net (code "17") (name "Net-(D4-A)") (class "Default")
      (node (ref "C114") (pin "2") (pinfunction "2_2") (pintype "passive"))
      (node (ref "C115") (pin "2") (pinfunction "2_2") (pintype "passive"))
      (node (ref "D4") (pin "2") (pinfunction "A_2") (pintype "passive"))
      (node (ref "L8") (pin "1") (pinfunction "1_1") (pintype "passive"))
      (node (ref "R117") (pin "2") (pinfunction "2_2") (pintype "passive"))
    )
    (net (code "18") (name "Net-(D4-C)") (class "Default")
      (node (ref "D4") (pin "1") (pinfunction "C_1") (pintype "passive"))
      (node (ref "IC35") (pin "20") (pinfunction "SW2_20") (pintype "output"))
      (node (ref "L9") (pin "1") (pinfunction "1_1") (pintype "passive"))
    )
    (net (code "19") (name "Net-(IC33A-IN-)") (class "Default")
      (node (ref "IC33") (pin "2") (pinfunction "IN-_2") (pintype "input"))
      (node (ref "RN5") (pin "2") (pinfunction "2_2") (pintype "passive"))
      (node (ref "RN5") (pin "6") (pinfunction "6_6") (pintype "passive"))
    )
    (net (code "20") (name "Net-(IC34-VOUTS)") (class "Default")
      (node (ref "C96") (pin "2") (pinfunction "2_2") (pintype "passive"))
      (node (ref "IC34") (pin "6") (pinfunction "VOUTS_6") (pintype "power_in"))
      (node (ref "R129") (pin "1") (pinfunction "1_1") (pintype "passive"))
    )
    (net (code "21") (name "Net-(IC34-~{SHDN})") (class "Default")
      (node (ref "IC34") (pin "1") (pinfunction "~{SHDN}_1") (pintype "input"))
      (node (ref "R127") (pin "1") (pinfunction "1_1") (pintype "passive"))
      (node (ref "R128") (pin "2") (pinfunction "2_2") (pintype "passive"))
    )
    (net (code "22") (name "Net-(IC35-FB1)") (class "Default")
      (node (ref "IC35") (pin "7") (pinfunction "FB1_7") (pintype "input"))
      (node (ref "R135") (pin "1") (pinfunction "1_1") (pintype "passive"))
      (node (ref "R139") (pin "2") (pinfunction "2_2") (pintype "passive"))
    )
    (net (code "23") (name "Net-(IC35-FB2)") (class "Default")
      (node (ref "IC35") (pin "13") (pinfunction "FB2_13") (pintype "input"))
      (node (ref "R117") (pin "1") (pinfunction "1_1") (pintype "passive"))
      (node (ref "R141") (pin "1") (pinfunction "1_1") (pintype "passive"))
    )
    (net (code "24") (name "Net-(IC35-INBK)") (class "Default")
      (node (ref "IC35") (pin "3") (pinfunction "INBK_3") (pintype "output"))
      (node (ref "L6") (pin "1") (pinfunction "1_1") (pintype "passive"))
    )
    (net (code "25") (name "Net-(IC35-VREF)") (class "Default")
      (node (ref "C111") (pin "2") (pinfunction "2_2") (pintype "passive"))
      (node (ref "IC35") (pin "14") (pinfunction "VREF_14") (pintype "output"))
      (node (ref "R141") (pin "2") (pinfunction "2_2") (pintype "passive"))
    )
    (net (code "26") (name "Net-(IC36-ADJ)") (class "Default")
      (node (ref "IC36") (pin "5") (pinfunction "ADJ_5") (pintype "input"))
      (node (ref "R136") (pin "1") (pinfunction "1_1") (pintype "passive"))
      (node (ref "R140") (pin "2") (pinfunction "2_2") (pintype "passive"))
    )
    (net (code "27") (name "Net-(IC36-BYP)") (class "Default")
      (node (ref "C110") (pin "2") (pinfunction "2_2") (pintype "passive"))
      (node (ref "IC36") (pin "6") (pinfunction "BYP_6") (pintype "passive"))
    )
    (net (code "28") (name "Net-(IC37-ADJ)") (class "Default")
      (node (ref "IC37") (pin "4") (pinfunction "ADJ_4") (pintype "input"))
      (node (ref "R126") (pin "1") (pinfunction "1_1") (pintype "passive"))
      (node (ref "R145") (pin "2") (pinfunction "2_2") (pintype "passive"))
    )
    (net (code "29") (name "Net-(IC38-EN)") (class "Default")
      (node (ref "C122") (pin "1") (pinfunction "1_1") (pintype "passive"))
      (node (ref "C123") (pin "2") (pinfunction "2_2") (pintype "passive"))
      (node (ref "IC38") (pin "1") (pinfunction "EN_1") (pintype "input"))
      (node (ref "IC38") (pin "2") (pinfunction "VIN_2") (pintype "input"))
      (node (ref "L10") (pin "2") (pinfunction "2_2") (pintype "passive"))
    )
    (net (code "30") (name "Net-(IC38-FB)") (class "Default")
      (node (ref "IC38") (pin "6") (pinfunction "FB_6") (pintype "output"))
      (node (ref "R147") (pin "1") (pinfunction "1_1") (pintype "passive"))
      (node (ref "R148") (pin "2") (pinfunction "2_2") (pintype "passive"))
    )
    (net (code "31") (name "Net-(IC39-IN-Pad1)") (class "Default")
      (node (ref "IC39") (pin "1") (pinfunction "IN_1") (pintype "input"))
      (node (ref "IC39") (pin "2") (pinfunction "IN_2") (pintype "input"))
      (node (ref "L12") (pin "2") (pinfunction "2_2") (pintype "passive"))
    )
    (net (code "32") (name "Net-(IC39-PGFB)") (class "Default")
      (node (ref "IC39") (pin "6") (pinfunction "PGFB_6") (pintype "input"))
      (node (ref "R151") (pin "2") (pinfunction "2_2") (pintype "passive"))
      (node (ref "R152") (pin "1") (pinfunction "1_1") (pintype "passive"))
    )
    (net (code "33") (name "Net-(IC39-SET)") (class "Default")
      (node (ref "C130") (pin "1") (pinfunction "1_1") (pintype "passive"))
      (node (ref "IC39") (pin "7") (pinfunction "SET_7") (pintype "input"))
      (node (ref "R149") (pin "1") (pinfunction "1_1") (pintype "passive"))
    )
    (net (code "34") (name "Net-(R130-Pad2)") (class "Default")
      (node (ref "R130") (pin "2") (pinfunction "2_2") (pintype "passive"))
      (node (ref "R140") (pin "1") (pinfunction "1_1") (pintype "passive"))
    )
    (net (code "35") (name "Net-(R149-Pad2)") (class "Default")
      (node (ref "R149") (pin "2") (pinfunction "2_2") (pintype "passive"))
      (node (ref "R150") (pin "1") (pinfunction "1_1") (pintype "passive"))
    )
    (net (code "36") (name "Net-(R152-Pad2)") (class "Default")
      (node (ref "R152") (pin "2") (pinfunction "2_2") (pintype "passive"))
      (node (ref "R153") (pin "1") (pinfunction "1_1") (pintype "passive"))
    )
    (net (code "37") (name "Net-(RN5-Pad5)") (class "Default")
      (node (ref "RN5") (pin "5") (pinfunction "5_5") (pintype "passive"))
      (node (ref "RN5") (pin "8") (pinfunction "8_8") (pintype "passive"))
    )
    (net (code "38") (name "P1V0_REF") (class "Default")
      (node (ref "IC31") (pin "1") (pinfunction "OUT_1") (pintype "output"))
      (node (ref "IC31") (pin "4") (pinfunction "IN-_4") (pintype "input"))
    )
    (net (code "39") (name "P2V0_REF") (class "Default")
      (node (ref "IC33") (pin "6") (pinfunction "IN-_6") (pintype "input"))
      (node (ref "IC33") (pin "7") (pinfunction "OUT_7") (pintype "output"))
    )
    (net (code "40") (name "P3V3") (class "Default")
      (node (ref "C129") (pin "2") (pinfunction "2_2") (pintype "passive"))
      (node (ref "IC38") (pin "4") (pinfunction "VOUT_4") (pintype "passive"))
      (node (ref "IC38") (pin "5") (pinfunction "VOUT_5") (pintype "power_in"))
      (node (ref "R147") (pin "2") (pinfunction "2_2") (pintype "passive"))
    )
    (net (code "41") (name "P5V0_REF") (class "Default")
      (node (ref "C97") (pin "2") (pinfunction "2_2") (pintype "passive"))
      (node (ref "IC34") (pin "7") (pinfunction "VOUTF_7") (pintype "power_in"))
      (node (ref "R129") (pin "2") (pinfunction "2_2") (pintype "passive"))
      (node (ref "RN5") (pin "4") (pinfunction "4_4") (pintype "passive"))
    )
    (net (code "42") (name "P5V4A") (class "Default")
      (node (ref "C126") (pin "2") (pinfunction "2_2") (pintype "passive"))
      (node (ref "C127") (pin "2") (pinfunction "2_2") (pintype "passive"))
      (node (ref "C128") (pin "2") (pinfunction "2_2") (pintype "passive"))
      (node (ref "C93") (pin "2") (pinfunction "2_2") (pintype "passive"))
      (node (ref "IC34") (pin "2") (pinfunction "VIN_2") (pintype "input"))
      (node (ref "IC39") (pin "10") (pinfunction "OUT_10") (pintype "output"))
      (node (ref "IC39") (pin "9") (pinfunction "OUTS_9") (pintype "output"))
      (node (ref "R128") (pin "1") (pinfunction "1_1") (pintype "passive"))
      (node (ref "R153") (pin "2") (pinfunction "2_2") (pintype "passive"))
    )
    (net (code "43") (name "P6V0_REF") (class "Default")
      (node (ref "IC33") (pin "1") (pinfunction "OUT_1") (pintype "output"))
      (node (ref "RN5") (pin "7") (pinfunction "7_7") (pintype "passive"))
    )
    (net (code "44") (name "P12V0_PS") (class "Default")
      (node (ref "C133") (pin "1") (pinfunction "1_1") (pintype "passive"))
      (node (ref "C134") (pin "2") (pinfunction "2_2") (pintype "passive"))
      (node (ref "C141") (pin "1") (pinfunction "1_1") (pintype "passive"))
      (node (ref "C142") (pin "2") (pinfunction "2_2") (pintype "passive"))
      (node (ref "L14") (pin "2") (pinfunction "2_2") (pintype "passive"))
    )
    (net (code "45") (name "P12V0p") (class "Default")
      (node (ref "C119") (pin "2") (pinfunction "2_2") (pintype "passive"))
      (node (ref "C120") (pin "2") (pinfunction "2_2") (pintype "passive"))
      (node (ref "C121") (pin "2") (pinfunction "2_2") (pintype "passive"))
      (node (ref "IC35") (pin "11") (pinfunction "EN2_11") (pintype "input"))
      (node (ref "IC35") (pin "17") (pinfunction "PVIN1_17") (pintype "power_in"))
      (node (ref "IC35") (pin "18") (pinfunction "PVINSYSS_18") (pintype "power_in"))
      (node (ref "IC35") (pin "19") (pinfunction "PVIN2_19") (pintype "power_in"))
      (node (ref "IC35") (pin "9") (pinfunction "EN1_9") (pintype "input"))
      (node (ref "L10") (pin "1") (pinfunction "1_1") (pintype "passive"))
      (node (ref "L11") (pin "1") (pinfunction "1_1") (pintype "passive"))
      (node (ref "L13") (pin "1") (pinfunction "1_1") (pintype "passive"))
    )
    (net (code "46") (name "P15V0") (class "Default")
      (node (ref "C105") (pin "2") (pinfunction "2_2") (pintype "passive"))
      (node (ref "C94") (pin "2") (pinfunction "2_2") (pintype "passive"))
      (node (ref "C98") (pin "2") (pinfunction "2_2") (pintype "passive"))
      (node (ref "IC31") (pin "5") (pinfunction "V+_5") (pintype "power_in"))
      (node (ref "IC33") (pin "8") (pinfunction "V+_8") (pintype "power_in"))
      (node (ref "IC36") (pin "2") (pinfunction "OUT_2") (pintype "power_in"))
      (node (ref "IC36") (pin "3") (pinfunction "OUT_3") (pintype "power_in"))
      (node (ref "R136") (pin "2") (pinfunction "2_2") (pintype "passive"))
    )
    (net (code "47") (name "P16V0") (class "Default")
      (node (ref "C100") (pin "1") (pinfunction "1_1") (pintype "passive"))
      (node (ref "C101") (pin "2") (pinfunction "2_2") (pintype "passive"))
      (node (ref "C104") (pin "2") (pinfunction "2_2") (pintype "passive"))
      (node (ref "IC36") (pin "10") (pinfunction "IN_10") (pintype "input"))
      (node (ref "IC36") (pin "11") (pinfunction "IN_11") (pintype "input"))
      (node (ref "IC36") (pin "8") (pinfunction "~{SHDN}_8") (pintype "input"))
      (node (ref "L7") (pin "2") (pinfunction "2_2") (pintype "passive"))
    )
    (net (code "48") (name "unconnected-(IC35-SS-Pad10)") (class "Default")
      (node (ref "IC35") (pin "10") (pinfunction "SS_10") (pintype "input+no_connect"))
    )
    (net (code "49") (name "unconnected-(IC36-NC-Pad1)") (class "Default")
      (node (ref "IC36") (pin "1") (pinfunction "NC_1") (pintype "passive"))
    )
    (net (code "50") (name "unconnected-(IC36-NC-Pad4)") (class "Default")
      (node (ref "IC36") (pin "4") (pinfunction "NC_4") (pintype "passive"))
    )
    (net (code "51") (name "unconnected-(IC36-NC-Pad9)") (class "Default")
      (node (ref "IC36") (pin "9") (pinfunction "NC_9") (pintype "passive"))
    )
    (net (code "52") (name "unconnected-(IC36-NC-Pad12)") (class "Default")
      (node (ref "IC36") (pin "12") (pinfunction "NC_12") (pintype "passive"))
    )
    (net (code "53") (name "unconnected-(IC38-PG-Pad7)") (class "Default")
      (node (ref "IC38") (pin "7") (pinfunction "PG_7") (pintype "output"))
    )
    (net (code "54") (name "unconnected-(IC38-VCC-Pad8)") (class "Default")
      (node (ref "IC38") (pin "8") (pinfunction "VCC_8") (pintype "power_in"))
    )
    (net (code "55") (name "unconnected-(IC39-PG-Pad4)") (class "Default")
      (node (ref "IC39") (pin "4") (pinfunction "PG_4") (pintype "output"))
    )
  )
)
